# whistle-board.net
KiCad netlist of a schematic drawn in EAGLE
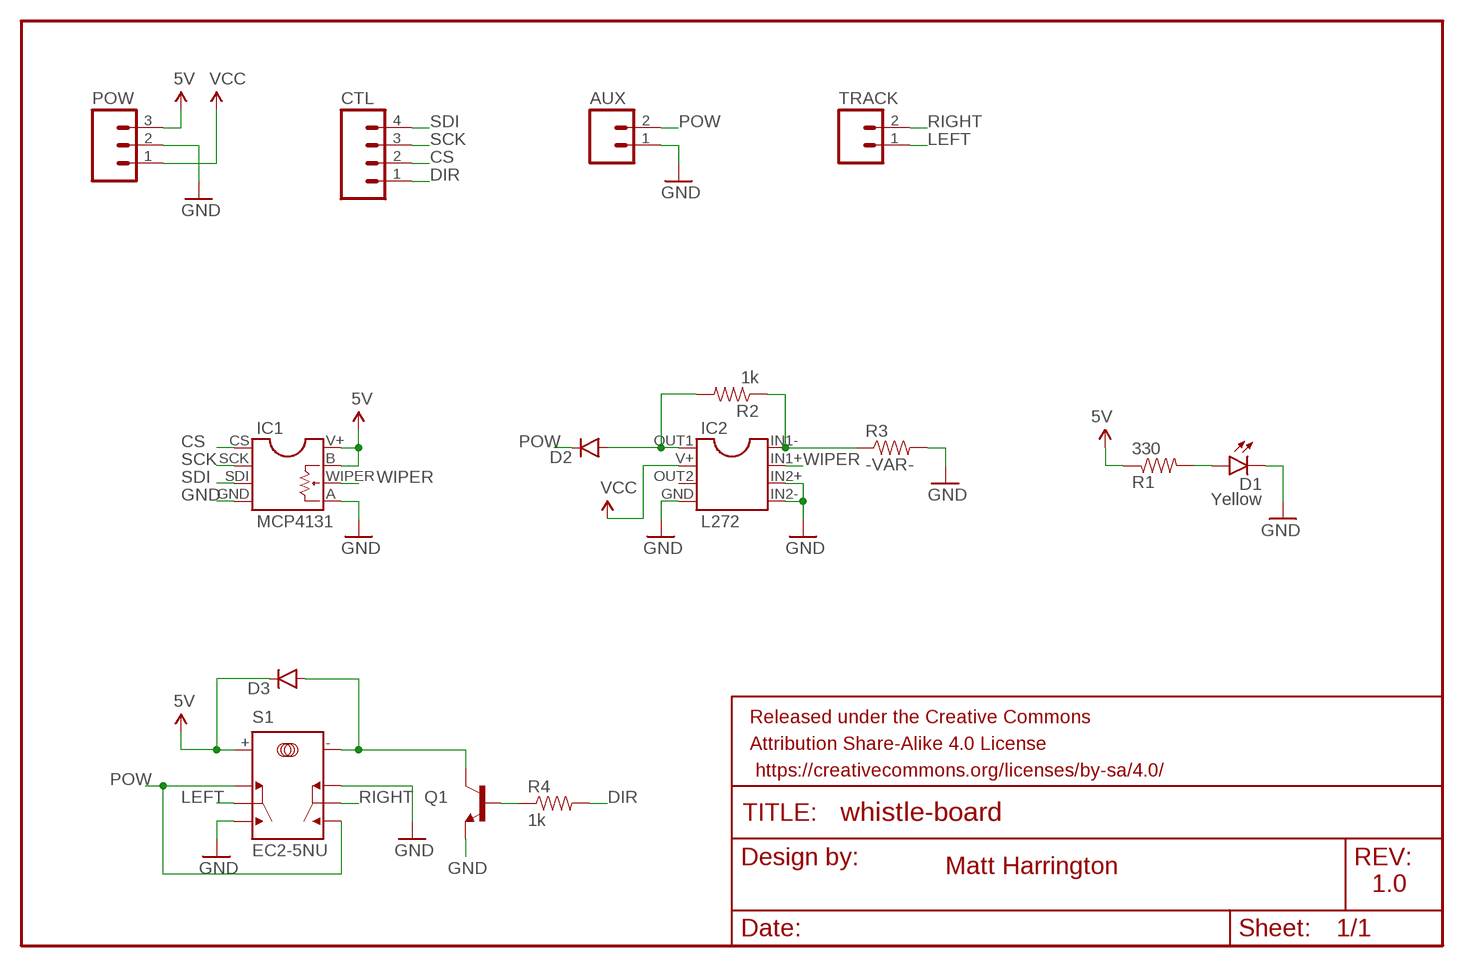
[diagram p0: schematic, sheet 1]

(export (version "E")
  (design (tool "Eeschema 10.0.6"))
  (components
    (comp (ref "AUX")
      (value "M02PTH")
      (footprint "eagle-import:1X02")
      (libsource (lib "eagle-import") (part "M02PTH"))
    )
    (comp (ref "CTL")
      (value "M04PTH")
      (footprint "eagle-import:1X04")
      (libsource (lib "eagle-import") (part "M04PTH"))
    )
    (comp (ref "D1")
      (value "Yellow")
      (footprint "eagle-import:LED-EDGE")
      (libsource (lib "eagle-import") (part "LED-YELLOW0603"))
    )
    (comp (ref "D2")
      (value "DIODEPTH")
      (footprint "eagle-import:DIODE-1N4001")
      (libsource (lib "eagle-import") (part "DIODEPTH"))
    )
    (comp (ref "D3")
      (value "DIODE1N4148")
      (footprint "eagle-import:DIODE-1N4148")
      (libsource (lib "eagle-import") (part "DIODE1N4148"))
    )
    (comp (ref "FRAME1")
      (value "FRAME-LETTER")
      (footprint "eagle-import:CREATIVE_COMMONS")
      (libsource (lib "eagle-import") (part "FRAME-LETTER"))
    )
    (comp (ref "IC1")
      (value "MCP4131")
      (footprint "eagle-import:MCP4131")
      (libsource (lib "eagle-import") (part "MCP4131"))
    )
    (comp (ref "IC2")
      (value "L272")
      (footprint "eagle-import:L272")
      (libsource (lib "eagle-import") (part "L272"))
    )
    (comp (ref "POW")
      (value "M03PTH")
      (footprint "eagle-import:1X03")
      (libsource (lib "eagle-import") (part "M03PTH"))
    )
    (comp (ref "Q1")
      (value "TRANSISTOR_NPNTO92")
      (footprint "eagle-import:TO-92")
      (libsource (lib "eagle-import") (part "TRANSISTOR_NPNTO92"))
    )
    (comp (ref "R1")
      (value "330")
      (footprint "eagle-import:AXIAL-0.3")
      (libsource (lib "eagle-import") (part "1KOHM-1/4W-5%(PTH)"))
    )
    (comp (ref "R2")
      (value "1k")
      (footprint "eagle-import:AXIAL-0.3")
      (libsource (lib "eagle-import") (part "1KOHM-1/4W-5%(PTH)"))
    )
    (comp (ref "R3")
      (value "-VAR-")
      (footprint "eagle-import:AXIAL-0.3")
      (libsource (lib "eagle-import") (part "1KOHM-1/4W-5%(PTH)"))
    )
    (comp (ref "R4")
      (value "1k")
      (footprint "eagle-import:AXIAL-0.3")
      (libsource (lib "eagle-import") (part "1KOHM-1/4W-5%(PTH)"))
    )
    (comp (ref "S1")
      (value "EC2-5NU")
      (footprint "eagle-import:EC2-5NU")
      (libsource (lib "eagle-import") (part "EC2-5NU"))
    )
    (comp (ref "TRACK")
      (value "M02PTH")
      (footprint "eagle-import:1X02")
      (libsource (lib "eagle-import") (part "M02PTH"))
    )
  )
  (nets
    (net (code "1") (name "/CS") (class "Default")
      (node (ref "CTL") (pin "2") (pinfunction "2_2") (pintype "passive"))
      (node (ref "IC1") (pin "CS") (pinfunction "CS_CS") (pintype "bidirectional"))
    )
    (net (code "2") (name "/DIR") (class "Default")
      (node (ref "CTL") (pin "1") (pinfunction "1_1") (pintype "passive"))
      (node (ref "R4") (pin "P$2") (pinfunction "2_P$2") (pintype "passive"))
    )
    (net (code "3") (name "/LEFT") (class "Default")
      (node (ref "S1") (pin "COM1") (pinfunction "COM1_COM1") (pintype "bidirectional"))
      (node (ref "TRACK") (pin "1") (pinfunction "1_1") (pintype "passive"))
    )
    (net (code "4") (name "/POW") (class "Default")
      (node (ref "AUX") (pin "2") (pinfunction "2_2") (pintype "passive"))
      (node (ref "D2") (pin "C") (pinfunction "C_C") (pintype "passive"))
      (node (ref "S1") (pin "NC1") (pinfunction "NC1_NC1") (pintype "bidirectional"))
      (node (ref "S1") (pin "NO2") (pinfunction "NO2_NO2") (pintype "bidirectional"))
    )
    (net (code "5") (name "/RIGHT") (class "Default")
      (node (ref "S1") (pin "COM2") (pinfunction "COM2_COM2") (pintype "bidirectional"))
      (node (ref "TRACK") (pin "2") (pinfunction "2_2") (pintype "passive"))
    )
    (net (code "6") (name "/SCK") (class "Default")
      (node (ref "CTL") (pin "3") (pinfunction "3_3") (pintype "passive"))
      (node (ref "IC1") (pin "SCK") (pinfunction "SCK_SCK") (pintype "bidirectional"))
    )
    (net (code "7") (name "/SDI") (class "Default")
      (node (ref "CTL") (pin "4") (pinfunction "4_4") (pintype "passive"))
      (node (ref "IC1") (pin "SDI") (pinfunction "SDI_SDI") (pintype "bidirectional"))
    )
    (net (code "8") (name "/WIPER") (class "Default")
      (node (ref "IC1") (pin "WIPER") (pinfunction "WIPER_WIPER") (pintype "bidirectional"))
      (node (ref "IC2") (pin "IN1+") (pinfunction "IN1+_IN1+") (pintype "bidirectional"))
    )
    (net (code "9") (name "5V") (class "Default")
      (node (ref "D3") (pin "C") (pinfunction "C_C") (pintype "passive"))
      (node (ref "IC1") (pin "B") (pinfunction "B_B") (pintype "bidirectional"))
      (node (ref "IC1") (pin "V+") (pinfunction "V+_V+") (pintype "bidirectional"))
      (node (ref "POW") (pin "3") (pinfunction "3_3") (pintype "passive"))
      (node (ref "R1") (pin "P$1") (pinfunction "1_P$1") (pintype "passive"))
      (node (ref "S1") (pin "+") (pinfunction "+_+") (pintype "power_in"))
    )
    (net (code "10") (name "GND") (class "Default")
      (node (ref "AUX") (pin "1") (pinfunction "1_1") (pintype "passive"))
      (node (ref "D1") (pin "C") (pinfunction "C_C") (pintype "passive"))
      (node (ref "IC1") (pin "A") (pinfunction "A_A") (pintype "bidirectional"))
      (node (ref "IC1") (pin "GND") (pinfunction "GND_GND") (pintype "bidirectional"))
      (node (ref "IC2") (pin "GND") (pinfunction "GND_GND") (pintype "bidirectional"))
      (node (ref "IC2") (pin "IN2+") (pinfunction "IN2+_IN2+") (pintype "bidirectional"))
      (node (ref "IC2") (pin "IN2-") (pinfunction "IN2-_IN2-") (pintype "bidirectional"))
      (node (ref "POW") (pin "2") (pinfunction "2_2") (pintype "passive"))
      (node (ref "Q1") (pin "1") (pinfunction "E_1") (pintype "passive"))
      (node (ref "R3") (pin "P$2") (pinfunction "2_P$2") (pintype "passive"))
      (node (ref "S1") (pin "NC2") (pinfunction "NC2_NC2") (pintype "bidirectional"))
      (node (ref "S1") (pin "NO1") (pinfunction "NO1_NO1") (pintype "bidirectional"))
    )
    (net (code "11") (name "Net-(Q1-B)") (class "Default")
      (node (ref "Q1") (pin "2") (pinfunction "B_2") (pintype "passive"))
      (node (ref "R4") (pin "P$1") (pinfunction "1_P$1") (pintype "passive"))
    )
    (net (code "12") (name "Net-(Q1-C)") (class "Default")
      (node (ref "D3") (pin "A") (pinfunction "A_A") (pintype "passive"))
      (node (ref "Q1") (pin "3") (pinfunction "C_3") (pintype "passive"))
      (node (ref "S1") (pin "-") (pinfunction "-_-") (pintype "power_in"))
    )
    (net (code "13") (name "Net-(R1-2)") (class "Default")
      (node (ref "D1") (pin "A") (pinfunction "A_A") (pintype "passive"))
      (node (ref "R1") (pin "P$2") (pinfunction "2_P$2") (pintype "passive"))
    )
    (net (code "14") (name "Net-(R2-1)") (class "Default")
      (node (ref "IC2") (pin "IN1-") (pinfunction "IN1-_IN1-") (pintype "bidirectional"))
      (node (ref "R2") (pin "P$1") (pinfunction "1_P$1") (pintype "passive"))
      (node (ref "R3") (pin "P$1") (pinfunction "1_P$1") (pintype "passive"))
    )
    (net (code "15") (name "Net-(R2-2)") (class "Default")
      (node (ref "D2") (pin "A") (pinfunction "A_A") (pintype "passive"))
      (node (ref "IC2") (pin "OUT1") (pinfunction "OUT1_OUT1") (pintype "bidirectional"))
      (node (ref "R2") (pin "P$2") (pinfunction "2_P$2") (pintype "passive"))
    )
    (net (code "16") (name "VCC") (class "Default")
      (node (ref "IC2") (pin "V+") (pinfunction "V+_V+") (pintype "bidirectional"))
      (node (ref "POW") (pin "1") (pinfunction "1_1") (pintype "passive"))
    )
    (net (code "17") (name "unconnected-(IC2-PadOUT2)") (class "Default")
      (node (ref "IC2") (pin "OUT2") (pinfunction "OUT2_OUT2") (pintype "bidirectional"))
    )
  )
)
